# ProtoCAT.net
KiCad netlist of a schematic drawn in EAGLE
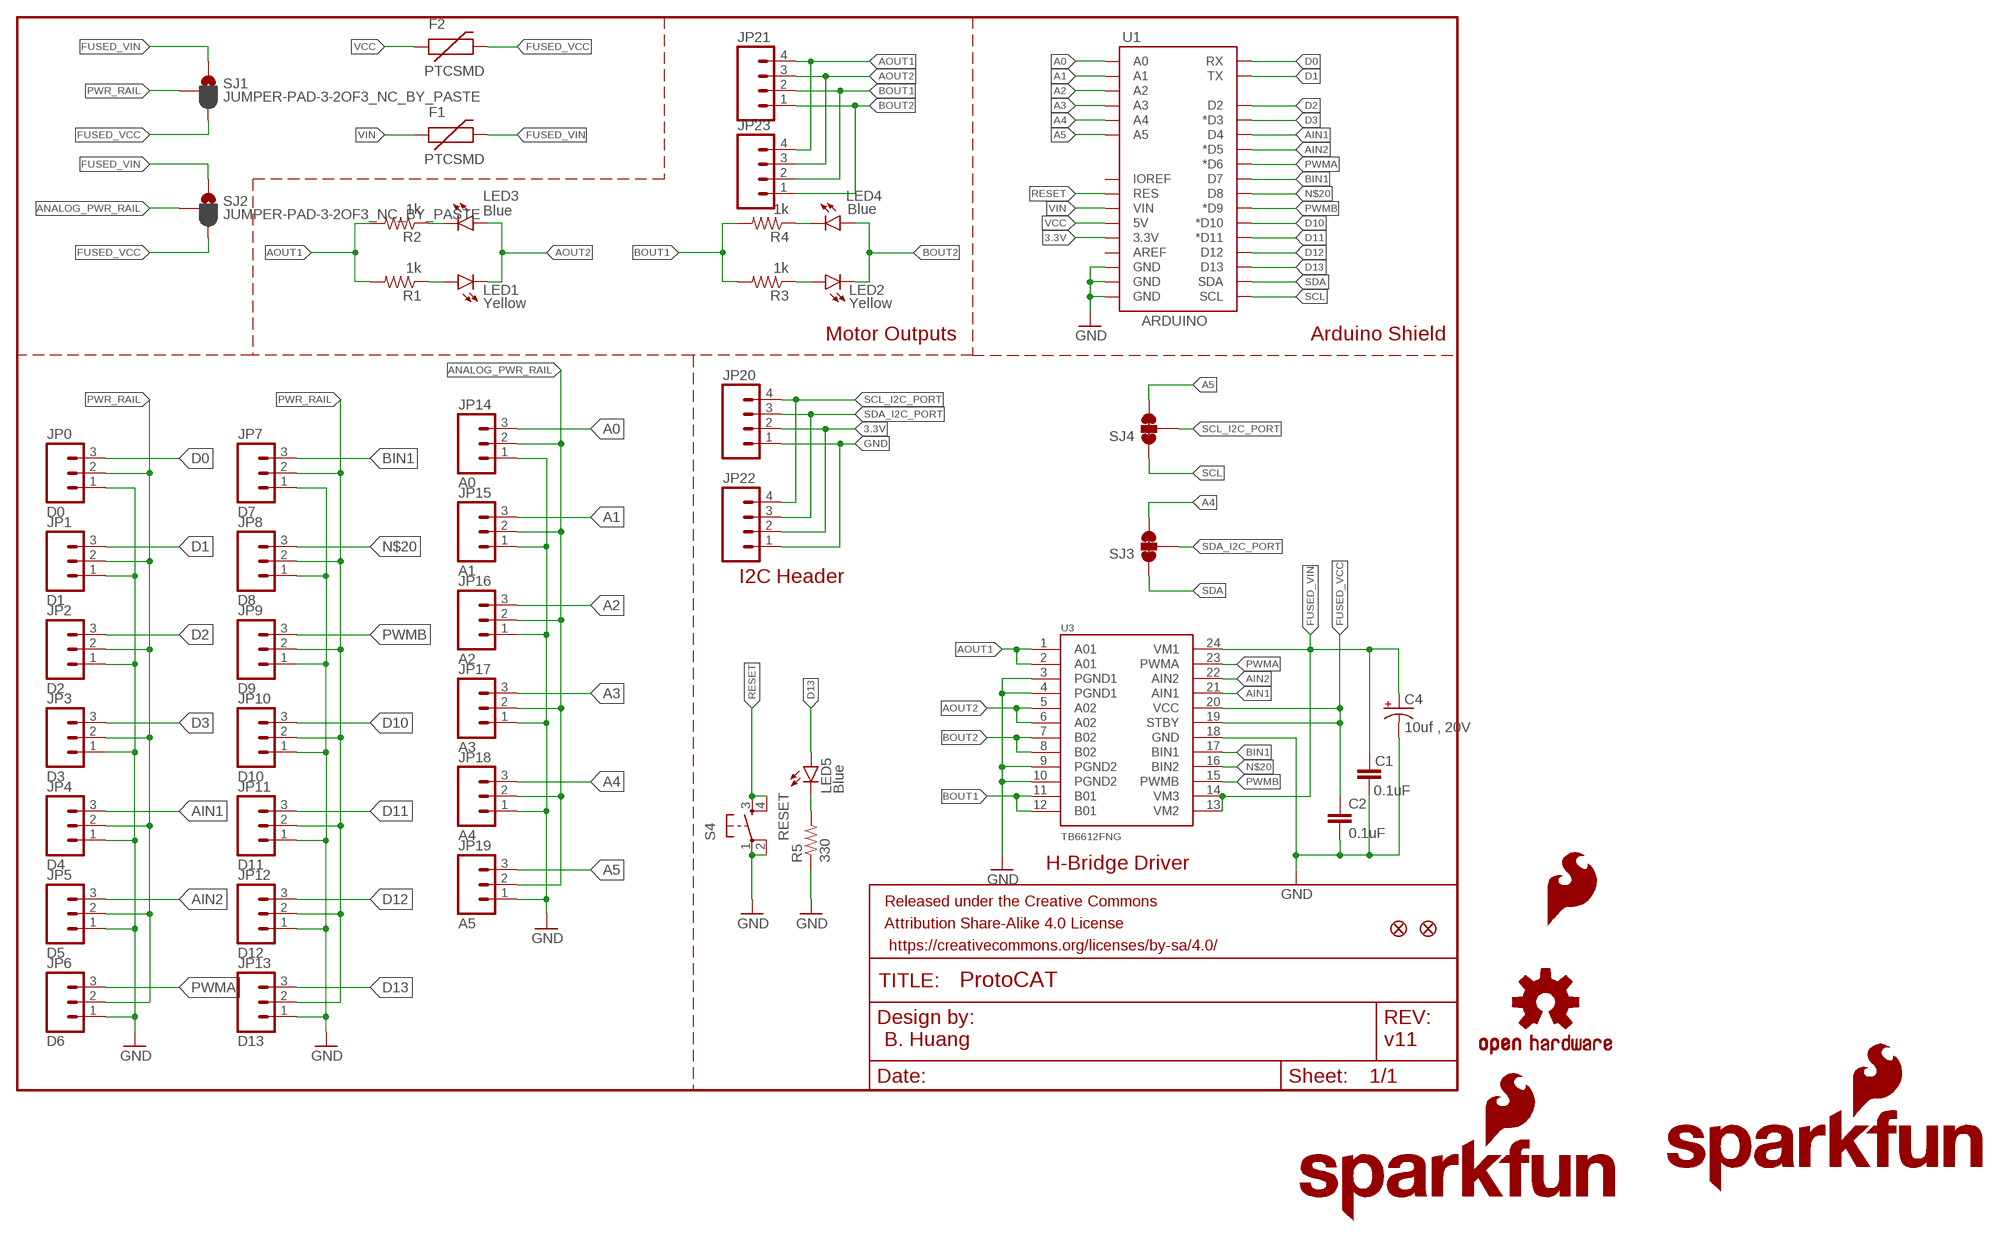
[diagram p0: schematic, sheet 1]

(export (version "E")
  (design (tool "Eeschema 10.0.6"))
  (components
    (comp (ref "C1")
      (value "0.1uF")
      (footprint "eagle-import:0603-CAP")
      (libsource (lib "eagle-import") (part "0.1UF-25V-5%(0603)"))
    )
    (comp (ref "C2")
      (value "0.1uF")
      (footprint "eagle-import:0603-CAP")
      (libsource (lib "eagle-import") (part "0.1UF-25V-5%(0603)"))
    )
    (comp (ref "C4")
      (value "10uf , 20V")
      (footprint "eagle-import:EIA3528")
      (libsource (lib "eagle-import") (part "10UF-20V-10%(TANT)"))
    )
    (comp (ref "F1")
      (value "PTCSMD")
      (footprint "eagle-import:PTC-1206")
      (libsource (lib "eagle-import") (part "PTCSMD"))
    )
    (comp (ref "F2")
      (value "PTCSMD")
      (footprint "eagle-import:PTC-1206")
      (libsource (lib "eagle-import") (part "PTCSMD"))
    )
    (comp (ref "FID1")
      (value "FIDUCIAL1X2")
      (footprint "eagle-import:FIDUCIAL-1X2")
      (libsource (lib "eagle-import") (part "FIDUCIAL1X2"))
    )
    (comp (ref "FID2")
      (value "FIDUCIAL1X2")
      (footprint "eagle-import:FIDUCIAL-1X2")
      (libsource (lib "eagle-import") (part "FIDUCIAL1X2"))
    )
    (comp (ref "FRAME1")
      (value "FRAME-LETTER")
      (footprint "eagle-import:CREATIVE_COMMONS")
      (libsource (lib "eagle-import") (part "FRAME-LETTER"))
    )
    (comp (ref "JP0")
      (value "D0")
      (footprint "eagle-import:1X03_LOCK")
      (libsource (lib "eagle-import") (part "M03LOCK"))
    )
    (comp (ref "JP1")
      (value "D1")
      (footprint "eagle-import:1X03_LOCK")
      (libsource (lib "eagle-import") (part "M03LOCK"))
    )
    (comp (ref "JP2")
      (value "D2")
      (footprint "eagle-import:1X03_LOCK")
      (libsource (lib "eagle-import") (part "M03LOCK"))
    )
    (comp (ref "JP3")
      (value "D3")
      (footprint "eagle-import:1X03_LOCK")
      (libsource (lib "eagle-import") (part "M03LOCK"))
    )
    (comp (ref "JP4")
      (value "D4")
      (footprint "eagle-import:1X03_LOCK")
      (libsource (lib "eagle-import") (part "M03LOCK"))
    )
    (comp (ref "JP5")
      (value "D5")
      (footprint "eagle-import:1X03_LOCK")
      (libsource (lib "eagle-import") (part "M03LOCK"))
    )
    (comp (ref "JP6")
      (value "D6")
      (footprint "eagle-import:1X03_LOCK")
      (libsource (lib "eagle-import") (part "M03LOCK"))
    )
    (comp (ref "JP7")
      (value "D7")
      (footprint "eagle-import:1X03_LOCK")
      (libsource (lib "eagle-import") (part "M03LOCK"))
    )
    (comp (ref "JP8")
      (value "D8")
      (footprint "eagle-import:1X03_LOCK")
      (libsource (lib "eagle-import") (part "M03LOCK"))
    )
    (comp (ref "JP9")
      (value "D9")
      (footprint "eagle-import:1X03_LOCK")
      (libsource (lib "eagle-import") (part "M03LOCK"))
    )
    (comp (ref "JP10")
      (value "D10")
      (footprint "eagle-import:1X03_LOCK")
      (libsource (lib "eagle-import") (part "M03LOCK"))
    )
    (comp (ref "JP11")
      (value "D11")
      (footprint "eagle-import:1X03_LOCK")
      (libsource (lib "eagle-import") (part "M03LOCK"))
    )
    (comp (ref "JP12")
      (value "D12")
      (footprint "eagle-import:1X03_LOCK")
      (libsource (lib "eagle-import") (part "M03LOCK"))
    )
    (comp (ref "JP13")
      (value "D13")
      (footprint "eagle-import:1X03_LOCK")
      (libsource (lib "eagle-import") (part "M03LOCK"))
    )
    (comp (ref "JP14")
      (value "A0")
      (footprint "eagle-import:1X03_LOCK")
      (libsource (lib "eagle-import") (part "M03LOCK"))
    )
    (comp (ref "JP15")
      (value "A1")
      (footprint "eagle-import:1X03_LOCK")
      (libsource (lib "eagle-import") (part "M03LOCK"))
    )
    (comp (ref "JP16")
      (value "A2")
      (footprint "eagle-import:1X03_LOCK")
      (libsource (lib "eagle-import") (part "M03LOCK"))
    )
    (comp (ref "JP17")
      (value "A3")
      (footprint "eagle-import:1X03_LOCK")
      (libsource (lib "eagle-import") (part "M03LOCK"))
    )
    (comp (ref "JP18")
      (value "A4")
      (footprint "eagle-import:1X03_LOCK")
      (libsource (lib "eagle-import") (part "M03LOCK"))
    )
    (comp (ref "JP19")
      (value "A5")
      (footprint "eagle-import:1X03_LOCK")
      (libsource (lib "eagle-import") (part "M03LOCK"))
    )
    (comp (ref "JP20")
      (value "M04SMD_STRAIGHT_COMBO")
      (footprint "eagle-import:1X04_SMD_STRAIGHT_COMBO")
      (libsource (lib "eagle-import") (part "M04SMD_STRAIGHT_COMBO"))
    )
    (comp (ref "JP21")
      (value "M04PTH")
      (footprint "eagle-import:1X04")
      (libsource (lib "eagle-import") (part "M04PTH"))
    )
    (comp (ref "JP22")
      (value "M04PTH")
      (footprint "eagle-import:1X04")
      (libsource (lib "eagle-import") (part "M04PTH"))
    )
    (comp (ref "JP23")
      (value "M04SMD_STRAIGHT_COMBO")
      (footprint "eagle-import:1X04_SMD_STRAIGHT_COMBO")
      (libsource (lib "eagle-import") (part "M04SMD_STRAIGHT_COMBO"))
    )
    (comp (ref "LED1")
      (value "Yellow")
      (footprint "eagle-import:LED-0603")
      (libsource (lib "eagle-import") (part "LED0603"))
    )
    (comp (ref "LED2")
      (value "Yellow")
      (footprint "eagle-import:LED-0603")
      (libsource (lib "eagle-import") (part "LED0603"))
    )
    (comp (ref "LED3")
      (value "Blue")
      (footprint "eagle-import:LED-0603")
      (libsource (lib "eagle-import") (part "LED0603"))
    )
    (comp (ref "LED4")
      (value "Blue")
      (footprint "eagle-import:LED-0603")
      (libsource (lib "eagle-import") (part "LED0603"))
    )
    (comp (ref "LED5")
      (value "Blue")
      (footprint "eagle-import:LED-0603")
      (libsource (lib "eagle-import") (part "LED0603"))
    )
    (comp (ref "LOGO1")
      (value "OSHW-LOGOM")
      (footprint "eagle-import:OSHW-LOGO-M")
      (libsource (lib "eagle-import") (part "OSHW-LOGOM"))
    )
    (comp (ref "LOGO2")
      (value "SFE_LOGO_NAME_FLAME.1_INCH")
      (footprint "eagle-import:SFE_LOGO_NAME_FLAME_.1")
      (libsource (lib "eagle-import") (part "SFE_LOGO_NAME_FLAME.1_INCH"))
    )
    (comp (ref "LOGO3")
      (value "SFE_LOGO_FLAME.2COP")
      (footprint "eagle-import:SFE_LOGO_FLAME_COPPER_.2")
      (libsource (lib "eagle-import") (part "SFE_LOGO_FLAME.2COP"))
    )
    (comp (ref "LOGO4")
      (value "SFE_LOGO_NAME_FLAME.1_INCH")
      (footprint "eagle-import:SFE_LOGO_NAME_FLAME_.1")
      (libsource (lib "eagle-import") (part "SFE_LOGO_NAME_FLAME.1_INCH"))
    )
    (comp (ref "R1")
      (value "1k")
      (footprint "eagle-import:0603-RES")
      (libsource (lib "eagle-import") (part "1KOHM1/10W1%(0603)"))
    )
    (comp (ref "R2")
      (value "1k")
      (footprint "eagle-import:0603-RES")
      (libsource (lib "eagle-import") (part "1KOHM1/10W1%(0603)"))
    )
    (comp (ref "R3")
      (value "1k")
      (footprint "eagle-import:0603-RES")
      (libsource (lib "eagle-import") (part "1KOHM1/10W1%(0603)"))
    )
    (comp (ref "R4")
      (value "1k")
      (footprint "eagle-import:0603-RES")
      (libsource (lib "eagle-import") (part "1KOHM1/10W1%(0603)"))
    )
    (comp (ref "R5")
      (value "330")
      (footprint "eagle-import:0603-RES")
      (libsource (lib "eagle-import") (part "330OHM1/10W1%(0603)"))
    )
    (comp (ref "S4")
      (value "RESET")
      (footprint "eagle-import:TACTILE-SWITCH-SMD")
      (libsource (lib "eagle-import") (part "TAC_SWITCHSMD"))
    )
    (comp (ref "SJ1")
      (value "JUMPER-PAD-3-2OF3_NC_BY_PASTE")
      (footprint "eagle-import:PAD-JUMPER-3-2OF3_NC_BY_PASTE_YES_SILK_FULL_BOX")
      (libsource (lib "eagle-import") (part "JUMPER-PAD-3-2OF3_NC_BY_PASTE"))
    )
    (comp (ref "SJ2")
      (value "JUMPER-PAD-3-2OF3_NC_BY_PASTE")
      (footprint "eagle-import:PAD-JUMPER-3-2OF3_NC_BY_PASTE_YES_SILK_FULL_BOX")
      (libsource (lib "eagle-import") (part "JUMPER-PAD-3-2OF3_NC_BY_PASTE"))
    )
    (comp (ref "SJ3")
      (value "JUMPER-PAD-3-NC_BY_TRACE")
      (footprint "eagle-import:PAD-JUMPER-3-3OF3_NC_BY_TRACE_YES_SILK_FULL_BOX")
      (libsource (lib "eagle-import") (part "JUMPER-PAD-3-NC_BY_TRACE"))
    )
    (comp (ref "SJ4")
      (value "JUMPER-PAD-3-NC_BY_TRACE")
      (footprint "eagle-import:PAD-JUMPER-3-3OF3_NC_BY_TRACE_YES_SILK_FULL_BOX")
      (libsource (lib "eagle-import") (part "JUMPER-PAD-3-NC_BY_TRACE"))
    )
    (comp (ref "U$1")
      (value "SFE_LUDUS")
      (footprint "eagle-import:SFE_LUDUS-M")
      (libsource (lib "eagle-import") (part "SFE_LUDUS"))
    )
    (comp (ref "U1")
      (value "ARDUINO")
      (footprint "eagle-import:UNO_R3_SHIELD_NOLABELS")
      (libsource (lib "eagle-import") (part "ARDUINO_R3_SHIELDNOLABELS"))
    )
    (comp (ref "U3")
      (value "TB6612FNG")
      (footprint "eagle-import:SSOP24")
      (libsource (lib "eagle-import") (part "TB6612FNG"))
    )
  )
  (nets
    (net (code "1") (name "3.3V") (class "Default")
      (node (ref "JP20") (pin "2") (pinfunction "2_2") (pintype "passive"))
      (node (ref "JP22") (pin "2") (pinfunction "2_2") (pintype "passive"))
      (node (ref "U1") (pin "3.3V") (pinfunction "3.3V_3.3V") (pintype "bidirectional"))
    )
    (net (code "2") (name "A0") (class "Default")
      (node (ref "JP14") (pin "3") (pinfunction "3_3") (pintype "passive"))
      (node (ref "U1") (pin "A0") (pinfunction "A0_A0") (pintype "bidirectional"))
    )
    (net (code "3") (name "A1") (class "Default")
      (node (ref "JP15") (pin "3") (pinfunction "3_3") (pintype "passive"))
      (node (ref "U1") (pin "A1") (pinfunction "A1_A1") (pintype "bidirectional"))
    )
    (net (code "4") (name "A2") (class "Default")
      (node (ref "JP16") (pin "3") (pinfunction "3_3") (pintype "passive"))
      (node (ref "U1") (pin "A2") (pinfunction "A2_A2") (pintype "bidirectional"))
    )
    (net (code "5") (name "A3") (class "Default")
      (node (ref "JP17") (pin "3") (pinfunction "3_3") (pintype "passive"))
      (node (ref "U1") (pin "A3") (pinfunction "A3_A3") (pintype "bidirectional"))
    )
    (net (code "6") (name "A4") (class "Default")
      (node (ref "JP18") (pin "3") (pinfunction "3_3") (pintype "passive"))
      (node (ref "SJ3") (pin "3") (pinfunction "3_3") (pintype "passive"))
      (node (ref "U1") (pin "A4") (pinfunction "A4_A4") (pintype "bidirectional"))
    )
    (net (code "7") (name "A5") (class "Default")
      (node (ref "JP19") (pin "3") (pinfunction "3_3") (pintype "passive"))
      (node (ref "SJ4") (pin "3") (pinfunction "3_3") (pintype "passive"))
      (node (ref "U1") (pin "A5") (pinfunction "A5_A5") (pintype "bidirectional"))
    )
    (net (code "8") (name "AIN1") (class "Default")
      (node (ref "JP4") (pin "3") (pinfunction "3_3") (pintype "passive"))
      (node (ref "U1") (pin "D4") (pinfunction "D4_D4") (pintype "bidirectional"))
      (node (ref "U3") (pin "21") (pinfunction "AIN1_21") (pintype "bidirectional"))
    )
    (net (code "9") (name "AIN2") (class "Default")
      (node (ref "JP5") (pin "3") (pinfunction "3_3") (pintype "passive"))
      (node (ref "U1") (pin "D5") (pinfunction "*D5_D5") (pintype "bidirectional"))
      (node (ref "U3") (pin "22") (pinfunction "AIN2_22") (pintype "bidirectional"))
    )
    (net (code "10") (name "ANALOG_PWR_RAIL") (class "Default")
      (node (ref "JP14") (pin "2") (pinfunction "2_2") (pintype "passive"))
      (node (ref "JP15") (pin "2") (pinfunction "2_2") (pintype "passive"))
      (node (ref "JP16") (pin "2") (pinfunction "2_2") (pintype "passive"))
      (node (ref "JP17") (pin "2") (pinfunction "2_2") (pintype "passive"))
      (node (ref "JP18") (pin "2") (pinfunction "2_2") (pintype "passive"))
      (node (ref "JP19") (pin "2") (pinfunction "2_2") (pintype "passive"))
      (node (ref "SJ2") (pin "2") (pinfunction "2_2") (pintype "passive"))
    )
    (net (code "11") (name "AOUT1") (class "Default")
      (node (ref "JP21") (pin "4") (pinfunction "4_4") (pintype "passive"))
      (node (ref "JP23") (pin "4") (pinfunction "4_4") (pintype "passive"))
      (node (ref "R1") (pin "2") (pinfunction "2_2") (pintype "passive"))
      (node (ref "R2") (pin "2") (pinfunction "2_2") (pintype "passive"))
      (node (ref "U3") (pin "1") (pinfunction "A01_1") (pintype "bidirectional"))
      (node (ref "U3") (pin "2") (pinfunction "A01_2") (pintype "bidirectional"))
    )
    (net (code "12") (name "AOUT2") (class "Default")
      (node (ref "JP21") (pin "3") (pinfunction "3_3") (pintype "passive"))
      (node (ref "JP23") (pin "3") (pinfunction "3_3") (pintype "passive"))
      (node (ref "LED1") (pin "C") (pinfunction "C_C") (pintype "passive"))
      (node (ref "LED3") (pin "A") (pinfunction "A_A") (pintype "passive"))
      (node (ref "U3") (pin "5") (pinfunction "A02_5") (pintype "bidirectional"))
      (node (ref "U3") (pin "6") (pinfunction "A02_6") (pintype "bidirectional"))
    )
    (net (code "13") (name "BIN1") (class "Default")
      (node (ref "JP7") (pin "3") (pinfunction "3_3") (pintype "passive"))
      (node (ref "U1") (pin "D7") (pinfunction "D7_D7") (pintype "bidirectional"))
      (node (ref "U3") (pin "17") (pinfunction "BIN1_17") (pintype "bidirectional"))
    )
    (net (code "14") (name "BOUT1") (class "Default")
      (node (ref "JP21") (pin "2") (pinfunction "2_2") (pintype "passive"))
      (node (ref "JP23") (pin "2") (pinfunction "2_2") (pintype "passive"))
      (node (ref "R3") (pin "2") (pinfunction "2_2") (pintype "passive"))
      (node (ref "R4") (pin "2") (pinfunction "2_2") (pintype "passive"))
      (node (ref "U3") (pin "11") (pinfunction "B01_11") (pintype "bidirectional"))
      (node (ref "U3") (pin "12") (pinfunction "B01_12") (pintype "bidirectional"))
    )
    (net (code "15") (name "BOUT2") (class "Default")
      (node (ref "JP21") (pin "1") (pinfunction "1_1") (pintype "passive"))
      (node (ref "JP23") (pin "1") (pinfunction "1_1") (pintype "passive"))
      (node (ref "LED2") (pin "C") (pinfunction "C_C") (pintype "passive"))
      (node (ref "LED4") (pin "A") (pinfunction "A_A") (pintype "passive"))
      (node (ref "U3") (pin "7") (pinfunction "B02_7") (pintype "bidirectional"))
      (node (ref "U3") (pin "8") (pinfunction "B02_8") (pintype "bidirectional"))
    )
    (net (code "16") (name "D0") (class "Default")
      (node (ref "JP0") (pin "3") (pinfunction "3_3") (pintype "passive"))
      (node (ref "U1") (pin "RX") (pinfunction "RX_RX") (pintype "bidirectional"))
    )
    (net (code "17") (name "D1") (class "Default")
      (node (ref "JP1") (pin "3") (pinfunction "3_3") (pintype "passive"))
      (node (ref "U1") (pin "TX") (pinfunction "TX_TX") (pintype "bidirectional"))
    )
    (net (code "18") (name "D2") (class "Default")
      (node (ref "JP2") (pin "3") (pinfunction "3_3") (pintype "passive"))
      (node (ref "U1") (pin "D2") (pinfunction "D2_D2") (pintype "bidirectional"))
    )
    (net (code "19") (name "D3") (class "Default")
      (node (ref "JP3") (pin "3") (pinfunction "3_3") (pintype "passive"))
      (node (ref "U1") (pin "D3") (pinfunction "*D3_D3") (pintype "bidirectional"))
    )
    (net (code "20") (name "D10") (class "Default")
      (node (ref "JP10") (pin "3") (pinfunction "3_3") (pintype "passive"))
      (node (ref "U1") (pin "D10") (pinfunction "*D10_D10") (pintype "bidirectional"))
    )
    (net (code "21") (name "D11") (class "Default")
      (node (ref "JP11") (pin "3") (pinfunction "3_3") (pintype "passive"))
      (node (ref "U1") (pin "D11") (pinfunction "*D11_D11") (pintype "bidirectional"))
    )
    (net (code "22") (name "D12") (class "Default")
      (node (ref "JP12") (pin "3") (pinfunction "3_3") (pintype "passive"))
      (node (ref "U1") (pin "D12") (pinfunction "D12_D12") (pintype "bidirectional"))
    )
    (net (code "23") (name "D13") (class "Default")
      (node (ref "JP13") (pin "3") (pinfunction "3_3") (pintype "passive"))
      (node (ref "LED5") (pin "A") (pinfunction "A_A") (pintype "passive"))
      (node (ref "U1") (pin "D13") (pinfunction "D13_D13") (pintype "bidirectional"))
    )
    (net (code "24") (name "FUSED_VCC") (class "Default")
      (node (ref "C2") (pin "1") (pinfunction "1_1") (pintype "passive"))
      (node (ref "F2") (pin "2") (pinfunction "2_2") (pintype "bidirectional"))
      (node (ref "SJ1") (pin "3") (pinfunction "3_3") (pintype "passive"))
      (node (ref "SJ2") (pin "3") (pinfunction "3_3") (pintype "passive"))
      (node (ref "U3") (pin "19") (pinfunction "STBY_19") (pintype "bidirectional"))
      (node (ref "U3") (pin "20") (pinfunction "VCC_20") (pintype "bidirectional"))
    )
    (net (code "25") (name "FUSED_VIN") (class "Default")
      (node (ref "C1") (pin "1") (pinfunction "1_1") (pintype "passive"))
      (node (ref "C4") (pin "A") (pinfunction "+_A") (pintype "passive"))
      (node (ref "F1") (pin "2") (pinfunction "2_2") (pintype "bidirectional"))
      (node (ref "SJ1") (pin "1") (pinfunction "1_1") (pintype "passive"))
      (node (ref "SJ2") (pin "1") (pinfunction "1_1") (pintype "passive"))
      (node (ref "U3") (pin "13") (pinfunction "VM2_13") (pintype "bidirectional"))
      (node (ref "U3") (pin "14") (pinfunction "VM3_14") (pintype "bidirectional"))
      (node (ref "U3") (pin "24") (pinfunction "VM1_24") (pintype "bidirectional"))
    )
    (net (code "26") (name "GND") (class "Default")
      (node (ref "C1") (pin "2") (pinfunction "2_2") (pintype "passive"))
      (node (ref "C2") (pin "2") (pinfunction "2_2") (pintype "passive"))
      (node (ref "C4") (pin "C") (pinfunction "-_C") (pintype "passive"))
      (node (ref "JP0") (pin "1") (pinfunction "1_1") (pintype "passive"))
      (node (ref "JP1") (pin "1") (pinfunction "1_1") (pintype "passive"))
      (node (ref "JP10") (pin "1") (pinfunction "1_1") (pintype "passive"))
      (node (ref "JP11") (pin "1") (pinfunction "1_1") (pintype "passive"))
      (node (ref "JP12") (pin "1") (pinfunction "1_1") (pintype "passive"))
      (node (ref "JP13") (pin "1") (pinfunction "1_1") (pintype "passive"))
      (node (ref "JP14") (pin "1") (pinfunction "1_1") (pintype "passive"))
      (node (ref "JP15") (pin "1") (pinfunction "1_1") (pintype "passive"))
      (node (ref "JP16") (pin "1") (pinfunction "1_1") (pintype "passive"))
      (node (ref "JP17") (pin "1") (pinfunction "1_1") (pintype "passive"))
      (node (ref "JP18") (pin "1") (pinfunction "1_1") (pintype "passive"))
      (node (ref "JP19") (pin "1") (pinfunction "1_1") (pintype "passive"))
      (node (ref "JP2") (pin "1") (pinfunction "1_1") (pintype "passive"))
      (node (ref "JP20") (pin "1") (pinfunction "1_1") (pintype "passive"))
      (node (ref "JP22") (pin "1") (pinfunction "1_1") (pintype "passive"))
      (node (ref "JP3") (pin "1") (pinfunction "1_1") (pintype "passive"))
      (node (ref "JP4") (pin "1") (pinfunction "1_1") (pintype "passive"))
      (node (ref "JP5") (pin "1") (pinfunction "1_1") (pintype "passive"))
      (node (ref "JP6") (pin "1") (pinfunction "1_1") (pintype "passive"))
      (node (ref "JP7") (pin "1") (pinfunction "1_1") (pintype "passive"))
      (node (ref "JP8") (pin "1") (pinfunction "1_1") (pintype "passive"))
      (node (ref "JP9") (pin "1") (pinfunction "1_1") (pintype "passive"))
      (node (ref "R5") (pin "1") (pinfunction "1_1") (pintype "passive"))
      (node (ref "S4") (pin "1") (pinfunction "1_1") (pintype "passive"))
      (node (ref "S4") (pin "2") (pinfunction "2_2") (pintype "passive"))
      (node (ref "U1") (pin "GND@0") (pinfunction "GND_GND@0") (pintype "bidirectional"))
      (node (ref "U1") (pin "GND@1") (pinfunction "GND_GND@1") (pintype "bidirectional"))
      (node (ref "U1") (pin "GND@2") (pinfunction "GND_GND@2") (pintype "bidirectional"))
      (node (ref "U3") (pin "10") (pinfunction "PGND2_10") (pintype "bidirectional"))
      (node (ref "U3") (pin "18") (pinfunction "GND_18") (pintype "bidirectional"))
      (node (ref "U3") (pin "3") (pinfunction "PGND1_3") (pintype "bidirectional"))
      (node (ref "U3") (pin "4") (pinfunction "PGND1_4") (pintype "bidirectional"))
      (node (ref "U3") (pin "9") (pinfunction "PGND2_9") (pintype "bidirectional"))
    )
    (net (code "27") (name "N$20") (class "Default")
      (node (ref "JP8") (pin "3") (pinfunction "3_3") (pintype "passive"))
      (node (ref "U1") (pin "D8") (pinfunction "D8_D8") (pintype "bidirectional"))
      (node (ref "U3") (pin "16") (pinfunction "BIN2_16") (pintype "bidirectional"))
    )
    (net (code "28") (name "Net-(LED1-PadA)") (class "Default")
      (node (ref "LED1") (pin "A") (pinfunction "A_A") (pintype "passive"))
      (node (ref "R1") (pin "1") (pinfunction "1_1") (pintype "passive"))
    )
    (net (code "29") (name "Net-(LED2-PadA)") (class "Default")
      (node (ref "LED2") (pin "A") (pinfunction "A_A") (pintype "passive"))
      (node (ref "R3") (pin "1") (pinfunction "1_1") (pintype "passive"))
    )
    (net (code "30") (name "Net-(LED3-PadC)") (class "Default")
      (node (ref "LED3") (pin "C") (pinfunction "C_C") (pintype "passive"))
      (node (ref "R2") (pin "1") (pinfunction "1_1") (pintype "passive"))
    )
    (net (code "31") (name "Net-(LED4-PadC)") (class "Default")
      (node (ref "LED4") (pin "C") (pinfunction "C_C") (pintype "passive"))
      (node (ref "R4") (pin "1") (pinfunction "1_1") (pintype "passive"))
    )
    (net (code "32") (name "Net-(LED5-PadC)") (class "Default")
      (node (ref "LED5") (pin "C") (pinfunction "C_C") (pintype "passive"))
      (node (ref "R5") (pin "2") (pinfunction "2_2") (pintype "passive"))
    )
    (net (code "33") (name "PWMA") (class "Default")
      (node (ref "JP6") (pin "3") (pinfunction "3_3") (pintype "passive"))
      (node (ref "U1") (pin "D6") (pinfunction "*D6_D6") (pintype "bidirectional"))
      (node (ref "U3") (pin "23") (pinfunction "PWMA_23") (pintype "bidirectional"))
    )
    (net (code "34") (name "PWMB") (class "Default")
      (node (ref "JP9") (pin "3") (pinfunction "3_3") (pintype "passive"))
      (node (ref "U1") (pin "D9") (pinfunction "*D9_D9") (pintype "bidirectional"))
      (node (ref "U3") (pin "15") (pinfunction "PWMB_15") (pintype "bidirectional"))
    )
    (net (code "35") (name "PWR_RAIL") (class "Default")
      (node (ref "JP0") (pin "2") (pinfunction "2_2") (pintype "passive"))
      (node (ref "JP1") (pin "2") (pinfunction "2_2") (pintype "passive"))
      (node (ref "JP10") (pin "2") (pinfunction "2_2") (pintype "passive"))
      (node (ref "JP11") (pin "2") (pinfunction "2_2") (pintype "passive"))
      (node (ref "JP12") (pin "2") (pinfunction "2_2") (pintype "passive"))
      (node (ref "JP13") (pin "2") (pinfunction "2_2") (pintype "passive"))
      (node (ref "JP2") (pin "2") (pinfunction "2_2") (pintype "passive"))
      (node (ref "JP3") (pin "2") (pinfunction "2_2") (pintype "passive"))
      (node (ref "JP4") (pin "2") (pinfunction "2_2") (pintype "passive"))
      (node (ref "JP5") (pin "2") (pinfunction "2_2") (pintype "passive"))
      (node (ref "JP6") (pin "2") (pinfunction "2_2") (pintype "passive"))
      (node (ref "JP7") (pin "2") (pinfunction "2_2") (pintype "passive"))
      (node (ref "JP8") (pin "2") (pinfunction "2_2") (pintype "passive"))
      (node (ref "JP9") (pin "2") (pinfunction "2_2") (pintype "passive"))
      (node (ref "SJ1") (pin "2") (pinfunction "2_2") (pintype "passive"))
    )
    (net (code "36") (name "RESET") (class "Default")
      (node (ref "S4") (pin "3") (pinfunction "3_3") (pintype "passive"))
      (node (ref "S4") (pin "4") (pinfunction "4_4") (pintype "passive"))
      (node (ref "U1") (pin "RES") (pinfunction "RES_RES") (pintype "bidirectional"))
    )
    (net (code "37") (name "SCL") (class "Default")
      (node (ref "SJ4") (pin "1") (pinfunction "1_1") (pintype "passive"))
      (node (ref "U1") (pin "SCL") (pinfunction "SCL_SCL") (pintype "bidirectional"))
    )
    (net (code "38") (name "SCL_I2C_PORT") (class "Default")
      (node (ref "JP20") (pin "4") (pinfunction "4_4") (pintype "passive"))
      (node (ref "JP22") (pin "4") (pinfunction "4_4") (pintype "passive"))
      (node (ref "SJ4") (pin "2") (pinfunction "2_2") (pintype "passive"))
    )
    (net (code "39") (name "SDA") (class "Default")
      (node (ref "SJ3") (pin "1") (pinfunction "1_1") (pintype "passive"))
      (node (ref "U1") (pin "SDA") (pinfunction "SDA_SDA") (pintype "bidirectional"))
    )
    (net (code "40") (name "SDA_I2C_PORT") (class "Default")
      (node (ref "JP20") (pin "3") (pinfunction "3_3") (pintype "passive"))
      (node (ref "JP22") (pin "3") (pinfunction "3_3") (pintype "passive"))
      (node (ref "SJ3") (pin "2") (pinfunction "2_2") (pintype "passive"))
    )
    (net (code "41") (name "VCC") (class "Default")
      (node (ref "F2") (pin "1") (pinfunction "1_1") (pintype "bidirectional"))
      (node (ref "U1") (pin "5V") (pinfunction "5V_5V") (pintype "bidirectional"))
    )
    (net (code "42") (name "VIN") (class "Default")
      (node (ref "F1") (pin "1") (pinfunction "1_1") (pintype "bidirectional"))
      (node (ref "U1") (pin "VIN") (pinfunction "VIN_VIN") (pintype "bidirectional"))
    )
    (net (code "43") (name "unconnected-(U1-PadAREF)") (class "Default")
      (node (ref "U1") (pin "AREF") (pinfunction "AREF_AREF") (pintype "bidirectional"))
    )
    (net (code "44") (name "unconnected-(U1-PadIOREF)") (class "Default")
      (node (ref "U1") (pin "IOREF") (pinfunction "IOREF_IOREF") (pintype "bidirectional"))
    )
  )
)
